# AC_voltage_sensor.net
KiCad netlist of a schematic drawn in Altium Designer
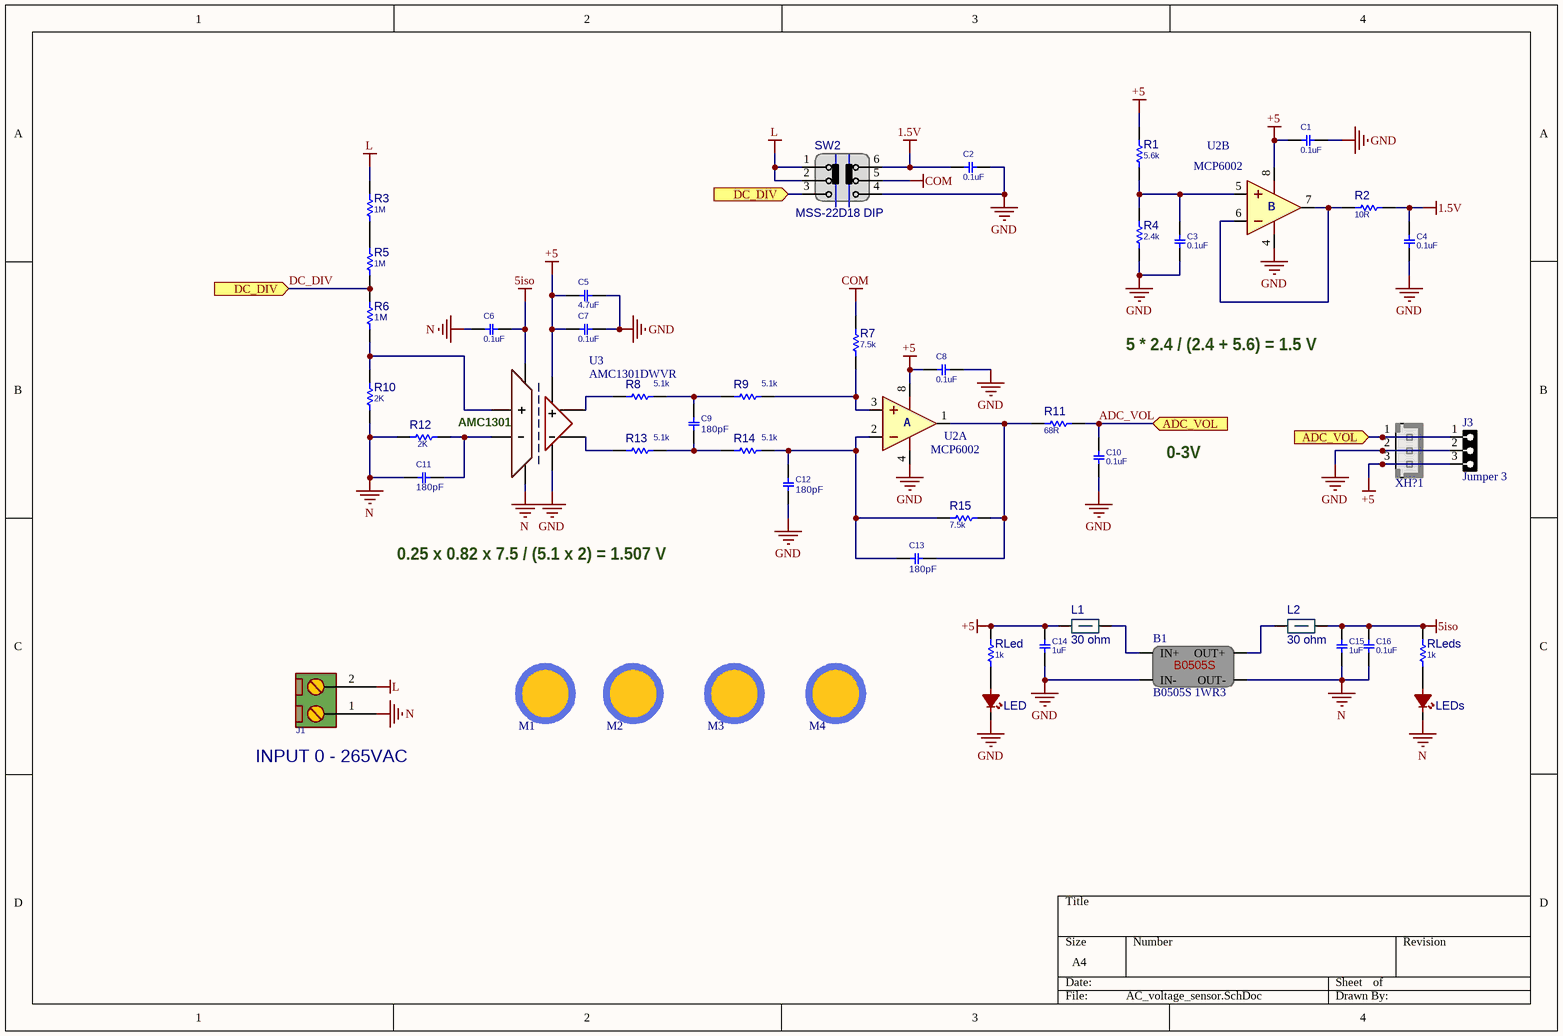
[diagram p0: AC_voltage_sensor.SchDoc]

(export (version "E")
  (design (tool "Eeschema 10.0.6"))
  (components
    (comp (ref "B1")
      (value "B0505S 1WR3")
      (footprint "B0505S")
      (description "B0505S 1WR3 Isolated Module DC DC Converter")
      (libsource (lib "IoT") (part "B0505S 1WR3"))
    )
    (comp (ref "C1")
      (value "0.1uF")
      (footprint "cap_0805")
      (description "CAP SMD")
      (fields (field (name "MANF_P#") "MANF_PART#"))
      (libsource (lib "IoT") (part "CAP SMD"))
    )
    (comp (ref "C2")
      (value "0.1uF")
      (footprint "cap_0805")
      (description "CAP SMD")
      (fields (field (name "MANF_P#") "MANF_PART#"))
      (libsource (lib "IoT") (part "CAP SMD"))
    )
    (comp (ref "C3")
      (value "0.1uF")
      (footprint "cap_0805")
      (description "CAP SMD")
      (fields (field (name "MANF_P#") "MANF_PART#"))
      (libsource (lib "IoT") (part "CAP SMD"))
    )
    (comp (ref "C4")
      (value "0.1uF")
      (footprint "cap_0805")
      (description "CAP SMD")
      (fields (field (name "MANF_P#") "MANF_PART#"))
      (libsource (lib "IoT") (part "CAP SMD"))
    )
    (comp (ref "C5")
      (value "4.7uF")
      (footprint "cap_0805")
      (description "CAP SMD")
      (fields (field (name "MANF_P#") "MANF_PART#"))
      (libsource (lib "IoT") (part "CAP SMD"))
    )
    (comp (ref "C6")
      (value "0.1uF")
      (footprint "cap_0805")
      (description "CAP SMD")
      (fields (field (name "MANF_P#") "MANF_PART#"))
      (libsource (lib "IoT") (part "CAP SMD"))
    )
    (comp (ref "C7")
      (value "0.1uF")
      (footprint "cap_0805")
      (description "CAP SMD")
      (fields (field (name "MANF_P#") "MANF_PART#"))
      (libsource (lib "IoT") (part "CAP SMD"))
    )
    (comp (ref "C8")
      (value "0.1uF")
      (footprint "cap_0805")
      (description "CAP SMD")
      (fields (field (name "MANF_P#") "MANF_PART#"))
      (libsource (lib "IoT") (part "CAP SMD"))
    )
    (comp (ref "C9")
      (value "180pF")
      (footprint "cap_0805")
      (description "CAP SMD")
      (fields (field (name "MANF_P#") "MANF_PART#"))
      (libsource (lib "IoT") (part "CAP SMD"))
    )
    (comp (ref "C10")
      (value "0.1uF")
      (footprint "cap_0805")
      (description "CAP SMD")
      (fields (field (name "MANF_P#") "MANF_PART#"))
      (libsource (lib "IoT") (part "CAP SMD"))
    )
    (comp (ref "C11")
      (value "180pF")
      (footprint "cap_0805")
      (description "CAP SMD")
      (fields (field (name "MANF_P#") "MANF_PART#"))
      (libsource (lib "IoT") (part "CAP SMD"))
    )
    (comp (ref "C12")
      (value "180pF")
      (footprint "cap_0805")
      (description "CAP SMD")
      (fields (field (name "MANF_P#") "MANF_PART#"))
      (libsource (lib "IoT") (part "CAP SMD"))
    )
    (comp (ref "C13")
      (value "180pF")
      (footprint "cap_0805")
      (description "CAP SMD")
      (fields (field (name "MANF_P#") "MANF_PART#"))
      (libsource (lib "IoT") (part "CAP SMD"))
    )
    (comp (ref "C14")
      (value "1uF")
      (footprint "cap_0805")
      (description "CAP SMD")
      (fields (field (name "MANF_P#") "MANF_PART#"))
      (libsource (lib "IoT") (part "CAP SMD"))
    )
    (comp (ref "C15")
      (value "1uF")
      (footprint "cap_0805")
      (description "CAP SMD")
      (fields (field (name "MANF_P#") "MANF_PART#"))
      (libsource (lib "IoT") (part "CAP SMD"))
    )
    (comp (ref "C16")
      (value "0.1uF")
      (footprint "cap_0805")
      (description "CAP SMD")
      (fields (field (name "MANF_P#") "MANF_PART#"))
      (libsource (lib "IoT") (part "CAP SMD"))
    )
    (comp (ref "J1")
      (value "CONN_TB2")
      (footprint "TBG_2")
      (description "CONN, TERMINAL BLOCK, 5.08mm pitch")
      (libsource (lib "IoT") (part "CONN_TB2"))
    )
    (comp (ref "J3") (value "Jumper 3") (footprint "JP3") (libsource (lib "IoT") (part "JP3")))
    (comp (ref "L1")
      (value "30 ohm")
      (footprint "fb0805")
      (description "Ferrite Bead, 30 ohm @ 100 MHz, 6 A, 0805")
      (fields (field (name "MANF_P#") "WSLP0805R0100FEA") (field (name "MANF") "VISHAY"))
      (libsource (lib "IoT") (part "RES SMD_1"))
    )
    (comp (ref "L2")
      (value "30 ohm")
      (footprint "fb0805")
      (description "Ferrite Bead, 30 ohm @ 100 MHz, 6 A, 0805")
      (fields (field (name "MANF_P#") "WSLP0805R0100FEA") (field (name "MANF") "VISHAY"))
      (libsource (lib "IoT") (part "RES SMD_1"))
    )
    (comp (ref "LED")
      (value "~")
      (footprint "LED0805RED")
      (description "LED Red SMD")
      (fields (field (name "MANF") "MANF") (field (name "MANF_P#") "MANF_PART#"))
      (libsource (lib "IoT") (part "LED Red SMD"))
    )
    (comp (ref "LEDs")
      (value "~")
      (footprint "LED0805RED")
      (description "LED Red SMD")
      (fields (field (name "MANF") "MANF") (field (name "MANF_P#") "MANF_PART#"))
      (libsource (lib "IoT") (part "LED Red SMD"))
    )
    (comp (ref "M1")
      (value "DNP/MH")
      (footprint "PSPMH3")
      (description "PSPMH3 Plastic Spacer mouting, Hole 3mm")
      (libsource (lib "IoT") (part "PSPMH3"))
    )
    (comp (ref "M2")
      (value "DNP/MH")
      (footprint "PSPMH3")
      (description "PSPMH3 Plastic Spacer mouting, Hole 3mm")
      (libsource (lib "IoT") (part "PSPMH3"))
    )
    (comp (ref "M3")
      (value "DNP/MH")
      (footprint "PSPMH3")
      (description "PSPMH3 Plastic Spacer mouting, Hole 3mm")
      (libsource (lib "IoT") (part "PSPMH3"))
    )
    (comp (ref "M4")
      (value "DNP/MH")
      (footprint "PSPMH3")
      (description "PSPMH3 Plastic Spacer mouting, Hole 3mm")
      (libsource (lib "IoT") (part "PSPMH3"))
    )
    (comp (ref "R1")
      (value "5.6k")
      (footprint "R0805")
      (description "RES SMD")
      (fields (field (name "MANF_P#") "WSLP0805R0100FEA") (field (name "MANF") "VISHAY"))
      (libsource (lib "IoT") (part "RES SMD"))
    )
    (comp (ref "R2")
      (value "10R")
      (footprint "R0805")
      (description "RES SMD")
      (fields (field (name "MANF_P#") "WSLP0805R0100FEA") (field (name "MANF") "VISHAY"))
      (libsource (lib "IoT") (part "RES SMD"))
    )
    (comp (ref "R3")
      (value "1M")
      (footprint "R0805")
      (description "RES SMD")
      (fields (field (name "MANF_P#") "WSLP0805R0100FEA") (field (name "MANF") "VISHAY"))
      (libsource (lib "IoT") (part "RES SMD"))
    )
    (comp (ref "R4")
      (value "2.4k")
      (footprint "R0805")
      (description "RES SMD")
      (fields (field (name "MANF_P#") "WSLP0805R0100FEA") (field (name "MANF") "VISHAY"))
      (libsource (lib "IoT") (part "RES SMD"))
    )
    (comp (ref "R5")
      (value "1M")
      (footprint "R0805")
      (description "RES SMD")
      (fields (field (name "MANF_P#") "WSLP0805R0100FEA") (field (name "MANF") "VISHAY"))
      (libsource (lib "") (part "RES SMD_1"))
    )
    (comp (ref "R6")
      (value "1M")
      (footprint "R0805")
      (description "RES SMD")
      (fields (field (name "MANF_P#") "WSLP0805R0100FEA") (field (name "MANF") "VISHAY"))
      (libsource (lib "IoT") (part "RES SMD"))
    )
    (comp (ref "R7")
      (value "7.5k")
      (footprint "R0805")
      (description "RES SMD")
      (fields (field (name "MANF_P#") "WSLP0805R0100FEA") (field (name "MANF") "VISHAY"))
      (libsource (lib "IoT") (part "RES SMD"))
    )
    (comp (ref "R8")
      (value "5.1k")
      (footprint "R0805")
      (description "RES SMD")
      (fields (field (name "MANF_P#") "WSLP0805R0100FEA") (field (name "MANF") "VISHAY"))
      (libsource (lib "IoT") (part "RES SMD"))
    )
    (comp (ref "R9")
      (value "5.1k")
      (footprint "R0805")
      (description "RES SMD")
      (fields (field (name "MANF_P#") "WSLP0805R0100FEA") (field (name "MANF") "VISHAY"))
      (libsource (lib "IoT") (part "RES SMD"))
    )
    (comp (ref "R10")
      (value "2K")
      (footprint "R0805")
      (description "RES SMD")
      (fields (field (name "MANF_P#") "WSLP0805R0100FEA") (field (name "MANF") "VISHAY"))
      (libsource (lib "IoT") (part "RES SMD"))
    )
    (comp (ref "R11")
      (value "68R")
      (footprint "R0805")
      (description "RES SMD")
      (fields (field (name "MANF_P#") "WSLP0805R0100FEA") (field (name "MANF") "VISHAY"))
      (libsource (lib "IoT") (part "RES SMD"))
    )
    (comp (ref "R12")
      (value "2K")
      (footprint "R0805")
      (description "RES SMD")
      (fields (field (name "MANF_P#") "WSLP0805R0100FEA") (field (name "MANF") "VISHAY"))
      (libsource (lib "IoT") (part "RES SMD"))
    )
    (comp (ref "R13")
      (value "5.1k")
      (footprint "R0805")
      (description "RES SMD")
      (fields (field (name "MANF_P#") "WSLP0805R0100FEA") (field (name "MANF") "VISHAY"))
      (libsource (lib "IoT") (part "RES SMD"))
    )
    (comp (ref "R14")
      (value "5.1k")
      (footprint "R0805")
      (description "RES SMD")
      (fields (field (name "MANF_P#") "WSLP0805R0100FEA") (field (name "MANF") "VISHAY"))
      (libsource (lib "IoT") (part "RES SMD"))
    )
    (comp (ref "R15")
      (value "7.5k")
      (footprint "R0805")
      (description "RES SMD")
      (fields (field (name "MANF_P#") "WSLP0805R0100FEA") (field (name "MANF") "VISHAY"))
      (libsource (lib "IoT") (part "RES SMD"))
    )
    (comp (ref "RLed")
      (value "1k")
      (footprint "R0805")
      (description "RES SMD")
      (fields (field (name "MANF_P#") "WSLP0805R0100FEA") (field (name "MANF") "VISHAY"))
      (libsource (lib "IoT") (part "RES SMD"))
    )
    (comp (ref "RLeds")
      (value "1k")
      (footprint "R0805")
      (description "RES SMD")
      (fields (field (name "MANF_P#") "WSLP0805R0100FEA") (field (name "MANF") "VISHAY"))
      (libsource (lib "IoT") (part "RES SMD"))
    )
    (comp (ref "SW2")
      (value "MSS-22D18 DIP")
      (footprint "SW_MS22D18")
      (description "SW MSS-22D18 Công Tắc Trượt 6 Chân ON-ON 2P2T 0.5A")
      (fields (field (name "MANF") "C&K") (field (name "MANF_PART#") "OS102011MS2QN1"))
      (libsource (lib "IoT") (part "SW MSS-22D18G2"))
    )
    (comp (ref "U2")
      (value "MCP6002")
      (footprint "Soic-8")
      (description "MCP6002  1MHz, Low-Power dual Op Amp")
      (fields (field (name "MF") "Microchip") (field (name "MP") "MCP1700T-3602E/MB"))
      (libsource (lib "IoT") (part "MCP6002"))
    )
    (comp (ref "U3")
      (value "AMC1301DWVR")
      (footprint "SOIC127P1150X280-8N")
      (description "AMC1301DWVR Isolation Amplifer, Opamp")
      (libsource (lib "IoT") (part "AMC1301DWVR"))
    )
    (comp (ref "XH?1")
      (value "HHDR_3")
      (footprint "XHN_3")
      (description "XHN 3 JST-XH pitch: 2.5mm")
      (libsource (lib "IoT") (part "XHN_3"))
    )
  )
  (nets
    (net (code "1") (name "+5") (class "Default")
      (node (ref "C1") (pin "1") (pinfunction "1_1") (pintype "passive"))
      (node (ref "C14") (pin "2") (pinfunction "2_2") (pintype "passive"))
      (node (ref "C5") (pin "1") (pinfunction "1_1") (pintype "passive"))
      (node (ref "C7") (pin "1") (pinfunction "1_1") (pintype "passive"))
      (node (ref "C8") (pin "1") (pinfunction "1_1") (pintype "passive"))
      (node (ref "J3") (pin "3") (pinfunction "3_3") (pintype "passive"))
      (node (ref "L1") (pin "1") (pinfunction "1_1") (pintype "passive"))
      (node (ref "R1") (pin "2") (pinfunction "2_2") (pintype "passive"))
      (node (ref "RLed") (pin "2") (pinfunction "2_2") (pintype "passive"))
      (node (ref "U2") (pin "8") (pinfunction "VDD_8") (pintype "passive"))
      (node (ref "U3") (pin "8") (pinfunction "VDD2_8") (pintype "passive"))
      (node (ref "XH?1") (pin "3") (pinfunction "3_3") (pintype "passive"))
    )
    (net (code "2") (name "/ADC_VOL") (class "Default")
      (node (ref "C10") (pin "2") (pinfunction "2_2") (pintype "passive"))
      (node (ref "J3") (pin "1") (pinfunction "1_1") (pintype "passive"))
      (node (ref "R11") (pin "2") (pinfunction "2_2") (pintype "passive"))
      (node (ref "XH?1") (pin "1") (pinfunction "1_1") (pintype "passive"))
    )
    (net (code "3") (name "/DC_DIV") (class "Default")
      (node (ref "R5") (pin "2") (pinfunction "2_2") (pintype "passive"))
      (node (ref "R6") (pin "2") (pinfunction "2_2") (pintype "passive"))
      (node (ref "SW2") (pin "3") (pinfunction "P4_3") (pintype "passive"))
    )
    (net (code "4") (name "1.5V") (class "Default")
      (node (ref "C2") (pin "2") (pinfunction "2_2") (pintype "passive"))
      (node (ref "C4") (pin "1") (pinfunction "1_1") (pintype "passive"))
      (node (ref "R2") (pin "1") (pinfunction "1_1") (pintype "passive"))
      (node (ref "SW2") (pin "6") (pinfunction "P1_6") (pintype "passive"))
    )
    (net (code "5") (name "5iso") (class "Default")
      (node (ref "C15") (pin "2") (pinfunction "2_2") (pintype "passive"))
      (node (ref "C16") (pin "2") (pinfunction "2_2") (pintype "passive"))
      (node (ref "C6") (pin "1") (pinfunction "1_1") (pintype "passive"))
      (node (ref "L2") (pin "2") (pinfunction "2_2") (pintype "passive"))
      (node (ref "RLeds") (pin "2") (pinfunction "2_2") (pintype "passive"))
      (node (ref "U3") (pin "1") (pinfunction "VDD1_1") (pintype "passive"))
    )
    (net (code "6") (name "COM") (class "Default")
      (node (ref "R7") (pin "2") (pinfunction "2_2") (pintype "passive"))
      (node (ref "SW2") (pin "5") (pinfunction "P3_5") (pintype "passive"))
    )
    (net (code "7") (name "GND") (class "Default")
      (node (ref "B1") (pin "1") (pinfunction "IN-_1") (pintype "passive"))
      (node (ref "C1") (pin "2") (pinfunction "2_2") (pintype "passive"))
      (node (ref "C10") (pin "1") (pinfunction "1_1") (pintype "passive"))
      (node (ref "C12") (pin "2") (pinfunction "2_2") (pintype "passive"))
      (node (ref "C14") (pin "1") (pinfunction "1_1") (pintype "passive"))
      (node (ref "C2") (pin "1") (pinfunction "1_1") (pintype "passive"))
      (node (ref "C3") (pin "2") (pinfunction "2_2") (pintype "passive"))
      (node (ref "C4") (pin "2") (pinfunction "2_2") (pintype "passive"))
      (node (ref "C5") (pin "2") (pinfunction "2_2") (pintype "passive"))
      (node (ref "C7") (pin "2") (pinfunction "2_2") (pintype "passive"))
      (node (ref "C8") (pin "2") (pinfunction "2_2") (pintype "passive"))
      (node (ref "J3") (pin "2") (pinfunction "2_2") (pintype "passive"))
      (node (ref "LED") (pin "2") (pinfunction "K_2") (pintype "passive"))
      (node (ref "R4") (pin "1") (pinfunction "1_1") (pintype "passive"))
      (node (ref "SW2") (pin "4") (pinfunction "P4_4") (pintype "passive"))
      (node (ref "U2") (pin "4") (pinfunction "VSS_4") (pintype "passive"))
      (node (ref "U3") (pin "5") (pinfunction "GND2_5") (pintype "passive"))
      (node (ref "XH?1") (pin "2") (pinfunction "2_2") (pintype "passive"))
    )
    (net (code "8") (name "L") (class "Default")
      (node (ref "J1") (pin "2") (pinfunction "2_2") (pintype "passive"))
      (node (ref "R3") (pin "2") (pinfunction "2_2") (pintype "passive"))
      (node (ref "SW2") (pin "1") (pinfunction "P1_1") (pintype "passive"))
      (node (ref "SW2") (pin "2") (pinfunction "P3_2") (pintype "passive"))
    )
    (net (code "9") (name "N") (class "Default")
      (node (ref "B1") (pin "3") (pinfunction "OUT-_3") (pintype "passive"))
      (node (ref "C11") (pin "2") (pinfunction "2_2") (pintype "passive"))
      (node (ref "C15") (pin "1") (pinfunction "1_1") (pintype "passive"))
      (node (ref "C16") (pin "1") (pinfunction "1_1") (pintype "passive"))
      (node (ref "C6") (pin "2") (pinfunction "2_2") (pintype "passive"))
      (node (ref "J1") (pin "1") (pinfunction "1_1") (pintype "passive"))
      (node (ref "LEDs") (pin "2") (pinfunction "K_2") (pintype "passive"))
      (node (ref "R10") (pin "1") (pinfunction "1_1") (pintype "passive"))
      (node (ref "R12") (pin "2") (pinfunction "2_2") (pintype "passive"))
      (node (ref "U3") (pin "4") (pinfunction "GND1_4") (pintype "passive"))
    )
    (net (code "10") (name "Net-(B1-IN+)") (class "Default")
      (node (ref "B1") (pin "2") (pinfunction "IN+_2") (pintype "passive"))
      (node (ref "L1") (pin "2") (pinfunction "2_2") (pintype "passive"))
    )
    (net (code "11") (name "Net-(B1-OUT+)") (class "Default")
      (node (ref "B1") (pin "4") (pinfunction "OUT+_4") (pintype "passive"))
      (node (ref "L2") (pin "1") (pinfunction "1_1") (pintype "passive"))
    )
    (net (code "12") (name "Net-(C9-Pad1)") (class "Default")
      (node (ref "C9") (pin "1") (pinfunction "1_1") (pintype "passive"))
      (node (ref "R8") (pin "1") (pinfunction "1_1") (pintype "passive"))
      (node (ref "R9") (pin "2") (pinfunction "2_2") (pintype "passive"))
    )
    (net (code "13") (name "Net-(C9-Pad2)") (class "Default")
      (node (ref "C9") (pin "2") (pinfunction "2_2") (pintype "passive"))
      (node (ref "R13") (pin "1") (pinfunction "1_1") (pintype "passive"))
      (node (ref "R14") (pin "2") (pinfunction "2_2") (pintype "passive"))
    )
    (net (code "14") (name "Net-(C11-Pad1)") (class "Default")
      (node (ref "C11") (pin "1") (pinfunction "1_1") (pintype "passive"))
      (node (ref "R12") (pin "1") (pinfunction "1_1") (pintype "passive"))
      (node (ref "U3") (pin "3") (pinfunction "-_3") (pintype "passive"))
    )
    (net (code "15") (name "Net-(LED-A)") (class "Default")
      (node (ref "LED") (pin "1") (pinfunction "A_1") (pintype "passive"))
      (node (ref "RLed") (pin "1") (pinfunction "1_1") (pintype "passive"))
    )
    (net (code "16") (name "Net-(LEDs-A)") (class "Default")
      (node (ref "LEDs") (pin "1") (pinfunction "A_1") (pintype "passive"))
      (node (ref "RLeds") (pin "1") (pinfunction "1_1") (pintype "passive"))
    )
    (net (code "17") (name "Net-(R3-Pad1)") (class "Default")
      (node (ref "R3") (pin "1") (pinfunction "1_1") (pintype "passive"))
      (node (ref "R5") (pin "1") (pinfunction "1_1") (pintype "passive"))
    )
    (net (code "18") (name "Net-(R8-Pad2)") (class "Default")
      (node (ref "R8") (pin "2") (pinfunction "2_2") (pintype "passive"))
      (node (ref "U3") (pin "7") (pinfunction "+_7") (pintype "passive"))
    )
    (net (code "19") (name "Net-(R10-Pad2)") (class "Default")
      (node (ref "R10") (pin "2") (pinfunction "2_2") (pintype "passive"))
      (node (ref "R6") (pin "1") (pinfunction "1_1") (pintype "passive"))
      (node (ref "U3") (pin "2") (pinfunction "+_2") (pintype "passive"))
    )
    (net (code "20") (name "Net-(R13-Pad2)") (class "Default")
      (node (ref "R13") (pin "2") (pinfunction "2_2") (pintype "passive"))
      (node (ref "U3") (pin "6") (pinfunction "-_6") (pintype "passive"))
    )
    (net (code "21") (name "Net-(U2A-IN+)") (class "Default")
      (node (ref "R7") (pin "1") (pinfunction "1_1") (pintype "passive"))
      (node (ref "R9") (pin "1") (pinfunction "1_1") (pintype "passive"))
      (node (ref "U2") (pin "3") (pinfunction "IN+_3") (pintype "passive"))
    )
    (net (code "22") (name "Net-(U2A-IN-)") (class "Default")
      (node (ref "C12") (pin "1") (pinfunction "1_1") (pintype "passive"))
      (node (ref "C13") (pin "1") (pinfunction "1_1") (pintype "passive"))
      (node (ref "R14") (pin "1") (pinfunction "1_1") (pintype "passive"))
      (node (ref "R15") (pin "1") (pinfunction "1_1") (pintype "passive"))
      (node (ref "U2") (pin "2") (pinfunction "IN-_2") (pintype "passive"))
    )
    (net (code "23") (name "Net-(U2A-OUT)") (class "Default")
      (node (ref "C13") (pin "2") (pinfunction "2_2") (pintype "passive"))
      (node (ref "R11") (pin "1") (pinfunction "1_1") (pintype "passive"))
      (node (ref "R15") (pin "2") (pinfunction "2_2") (pintype "passive"))
      (node (ref "U2") (pin "1") (pinfunction "OUT_1") (pintype "passive"))
    )
    (net (code "24") (name "Net-(U2B-IN+)") (class "Default")
      (node (ref "C3") (pin "1") (pinfunction "1_1") (pintype "passive"))
      (node (ref "R1") (pin "1") (pinfunction "1_1") (pintype "passive"))
      (node (ref "R4") (pin "2") (pinfunction "2_2") (pintype "passive"))
      (node (ref "U2") (pin "5") (pinfunction "IN+_5") (pintype "passive"))
    )
    (net (code "25") (name "Net-(U2B-IN-)") (class "Default")
      (node (ref "R2") (pin "2") (pinfunction "2_2") (pintype "passive"))
      (node (ref "U2") (pin "6") (pinfunction "IN-_6") (pintype "passive"))
      (node (ref "U2") (pin "7") (pinfunction "OUT_7") (pintype "passive"))
    )
  )
)
